# 1_P1.net
KiCad netlist of a schematic drawn in Altium Designer
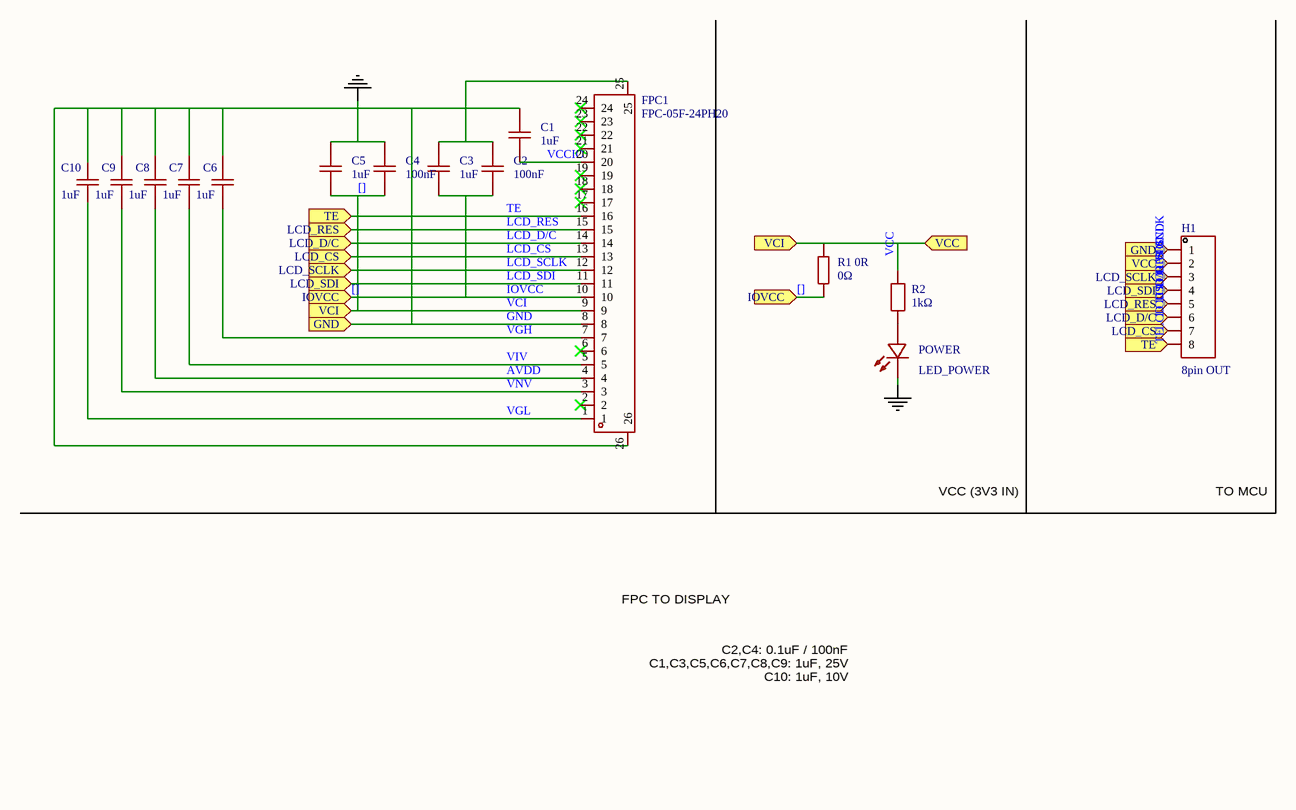
[diagram p0: 1_P1.schdoc]

(export (version "E")
  (design (tool "Eeschema 10.0.6"))
  (components
    (comp (ref "C1")
      (value "1uF")
      (footprint "C0402")
      (description "容值:1uF;精度:±10%;额定电压:25V;温度系数:X5R;")
      (fields
        (field (name "MANUFACTURER") "SAMSUNG(三星)")
        (field (name "MANUFACTURER PART") "CL05A105KA5NQNC")
      )
      (libsource (lib "altium-import") (part "root_1_CL05A105KA5NQNC_"))
    )
    (comp (ref "C2")
      (value "100nF")
      (footprint "C0402")
      (description "容值:100nF;精度:±10%;额定电压:50V;温度系数:X7R;")
      (fields
        (field (name "MANUFACTURER") "SAMSUNG(三星)")
        (field (name "MANUFACTURER PART") "CL05B104KB54PNC")
      )
      (libsource (lib "altium-import") (part "root_3_CL05B104KB54PNC_"))
    )
    (comp (ref "C3")
      (value "1uF")
      (footprint "C0402")
      (description "容值:1uF;精度:±10%;额定电压:25V;温度系数:X5R;")
      (fields
        (field (name "MANUFACTURER") "SAMSUNG(三星)")
        (field (name "MANUFACTURER PART") "CL05A105KA5NQNC")
      )
      (libsource (lib "altium-import") (part "root_3_CL05A105KA5NQNC_"))
    )
    (comp (ref "C4")
      (value "100nF")
      (footprint "C0402")
      (description "容值:100nF;精度:±10%;额定电压:50V;温度系数:X7R;")
      (fields
        (field (name "MANUFACTURER") "SAMSUNG(三星)")
        (field (name "MANUFACTURER PART") "CL05B104KB54PNC")
      )
      (libsource (lib "altium-import") (part "root_3_CL05B104KB54PNC_"))
    )
    (comp (ref "C5")
      (value "1uF")
      (footprint "C0402")
      (description "容值:1uF;精度:±10%;额定电压:25V;温度系数:X5R;")
      (fields
        (field (name "MANUFACTURER") "SAMSUNG(三星)")
        (field (name "MANUFACTURER PART") "CL05A105KA5NQNC")
      )
      (libsource (lib "altium-import") (part "root_3_CL05A105KA5NQNC_"))
    )
    (comp (ref "C6")
      (value "1uF")
      (footprint "C0402")
      (description "容值:1uF;精度:±10%;额定电压:25V;温度系数:X5R;")
      (fields
        (field (name "MANUFACTURER") "SAMSUNG(三星)")
        (field (name "MANUFACTURER PART") "CL05A105KA5NQNC")
      )
      (libsource (lib "altium-import") (part "root_3_CL05A105KA5NQNC_"))
    )
    (comp (ref "C7")
      (value "1uF")
      (footprint "C0402")
      (description "容值:1uF;精度:±10%;额定电压:25V;温度系数:X5R;")
      (fields
        (field (name "MANUFACTURER") "SAMSUNG(三星)")
        (field (name "MANUFACTURER PART") "CL05A105KA5NQNC")
      )
      (libsource (lib "altium-import") (part "root_3_CL05A105KA5NQNC_"))
    )
    (comp (ref "C8")
      (value "1uF")
      (footprint "C0402")
      (description "容值:1uF;精度:±10%;额定电压:25V;温度系数:X5R;")
      (fields
        (field (name "MANUFACTURER") "SAMSUNG(三星)")
        (field (name "MANUFACTURER PART") "CL05A105KA5NQNC")
      )
      (libsource (lib "altium-import") (part "root_3_CL05A105KA5NQNC_"))
    )
    (comp (ref "C9")
      (value "1uF")
      (footprint "C0402")
      (description "容值:1uF;精度:±10%;额定电压:25V;温度系数:X5R;")
      (fields
        (field (name "MANUFACTURER") "SAMSUNG(三星)")
        (field (name "MANUFACTURER PART") "CL05A105KA5NQNC")
      )
      (libsource (lib "altium-import") (part "root_3_CL05A105KA5NQNC_"))
    )
    (comp (ref "C10")
      (value "1uF")
      (footprint "C0402")
      (description "容值:1uF;精度:±10%;额定电压:10V;温度系数:X5R;")
      (fields
        (field (name "MANUFACTURER") "SAMSUNG(三星)")
        (field (name "MANUFACTURER PART") "CL05A105KP5NNNC")
      )
      (libsource (lib "altium-import") (part "root_3_CL05A105KP5NNNC_"))
    )
    (comp (ref "FPC1")
      (value "FPC-05F-24PH20")
      (footprint "FPC-SMD_24P-P0.50_FPC-05F-24PH20")
      (description "锁定特性:翻盖式;触点类型:卧贴;触点数量:24P;间距:0.5mm;安装方式:下接;工作温度:-25℃~+85℃;")
      (fields (field (name "MANUFACTURER") "XUNPU(讯普)"))
      (libsource (lib "altium-import") (part "root_2_mirrored_FPC-05F-24PH20_"))
    )
    (comp (ref "H1")
      (value "8pin OUT")
      (footprint "HDR-TH_8P-P2.54-V-M")
      (fields (field (name "MANUFACTURER") "Ckmtw(灿科盟)"))
      (libsource (lib "altium-import") (part "root_0_B-2100S08P-A110_"))
    )
    (comp (ref "POWER")
      (value "LED_POWER")
      (footprint "LED0603-RD-YELLOW")
      (fields (field (name "MANUFACTURER") "LITEON(光宝)"))
      (libsource (lib "altium-import") (part "root_1_LTST-C191KSKT_"))
    )
    (comp (ref "R1 0R")
      (value "0Ω")
      (footprint "R0805")
      (description "电阻类型:厚膜电阻;阻值:0Ω;精度:±1%;功率:125mW;工作电压:150V;温度系数:±800ppm/℃;")
      (fields
        (field (name "MANUFACTURER") "UNI-ROYAL(厚声)")
        (field (name "MANUFACTURER PART") "0805W8F0000T5E")
      )
      (libsource (lib "altium-import") (part "root_1_0805W8F0000T5E_"))
    )
    (comp (ref "R2")
      (value "1kΩ")
      (footprint "R0805")
      (description "电阻类型:厚膜电阻;阻值:1kΩ;精度:±5%;功率:125mW;工作电压:150V;温度系数:±100ppm/℃;")
      (fields (field (name "MANUFACTURER") "FOJAN(富捷)") (field (name "MANUFACTURER PART") "FRR0805J102 TS"))
      (libsource (lib "altium-import") (part "root_1_FRR0805J102 TS_"))
    )
  )
  (nets
    (net (code "1") (name "/AVDD") (class "Default")
      (node (ref "C8") (pin "2") (pinfunction "2_2") (pintype "passive"))
      (node (ref "FPC1") (pin "4") (pinfunction "4_4") (pintype "passive"))
    )
    (net (code "2") (name "/IOVCC") (class "Default")
      (node (ref "C2") (pin "2") (pinfunction "2_2") (pintype "passive"))
      (node (ref "C3") (pin "2") (pinfunction "2_2") (pintype "passive"))
      (node (ref "C4") (pin "2") (pinfunction "2_2") (pintype "passive"))
      (node (ref "C5") (pin "2") (pinfunction "2_2") (pintype "passive"))
      (node (ref "FPC1") (pin "10") (pinfunction "10_10") (pintype "passive"))
      (node (ref "FPC1") (pin "9") (pinfunction "9_9") (pintype "passive"))
      (node (ref "H1") (pin "2") (pinfunction "2_2") (pintype "passive"))
      (node (ref "R1 0R") (pin "1") (pinfunction "1_1") (pintype "passive"))
      (node (ref "R1 0R") (pin "2") (pinfunction "2_2") (pintype "passive"))
      (node (ref "R2") (pin "2") (pinfunction "2_2") (pintype "passive"))
    )
    (net (code "3") (name "/LCD_CS") (class "Default")
      (node (ref "FPC1") (pin "13") (pinfunction "13_13") (pintype "passive"))
      (node (ref "H1") (pin "7") (pinfunction "7_7") (pintype "passive"))
    )
    (net (code "4") (name "/LCD_D{slash}C") (class "Default")
      (node (ref "FPC1") (pin "14") (pinfunction "14_14") (pintype "passive"))
      (node (ref "H1") (pin "6") (pinfunction "6_6") (pintype "passive"))
    )
    (net (code "5") (name "/LCD_RES") (class "Default")
      (node (ref "FPC1") (pin "15") (pinfunction "15_15") (pintype "passive"))
      (node (ref "H1") (pin "5") (pinfunction "5_5") (pintype "passive"))
    )
    (net (code "6") (name "/LCD_SCLK") (class "Default")
      (node (ref "FPC1") (pin "12") (pinfunction "12_12") (pintype "passive"))
      (node (ref "H1") (pin "3") (pinfunction "3_3") (pintype "passive"))
    )
    (net (code "7") (name "/LCD_SDI") (class "Default")
      (node (ref "FPC1") (pin "11") (pinfunction "11_11") (pintype "passive"))
      (node (ref "H1") (pin "4") (pinfunction "4_4") (pintype "passive"))
    )
    (net (code "8") (name "/TE") (class "Default")
      (node (ref "FPC1") (pin "16") (pinfunction "16_16") (pintype "passive"))
      (node (ref "H1") (pin "8") (pinfunction "8_8") (pintype "passive"))
    )
    (net (code "9") (name "/VCCIO") (class "Default")
      (node (ref "C1") (pin "1") (pinfunction "1_1") (pintype "passive"))
      (node (ref "FPC1") (pin "20") (pinfunction "20_20") (pintype "passive"))
    )
    (net (code "10") (name "/VGH") (class "Default")
      (node (ref "C6") (pin "2") (pinfunction "2_2") (pintype "passive"))
      (node (ref "FPC1") (pin "7") (pinfunction "7_7") (pintype "passive"))
    )
    (net (code "11") (name "/VGL") (class "Default")
      (node (ref "C10") (pin "2") (pinfunction "2_2") (pintype "passive"))
      (node (ref "FPC1") (pin "1") (pinfunction "1_1") (pintype "passive"))
    )
    (net (code "12") (name "/VIV") (class "Default")
      (node (ref "C7") (pin "2") (pinfunction "2_2") (pintype "passive"))
      (node (ref "FPC1") (pin "5") (pinfunction "5_5") (pintype "passive"))
    )
    (net (code "13") (name "/VNV") (class "Default")
      (node (ref "C9") (pin "2") (pinfunction "2_2") (pintype "passive"))
      (node (ref "FPC1") (pin "3") (pinfunction "3_3") (pintype "passive"))
    )
    (net (code "14") (name "GND") (class "Default")
      (node (ref "C1") (pin "2") (pinfunction "2_2") (pintype "passive"))
      (node (ref "C10") (pin "1") (pinfunction "1_1") (pintype "passive"))
      (node (ref "C2") (pin "1") (pinfunction "1_1") (pintype "passive"))
      (node (ref "C3") (pin "1") (pinfunction "1_1") (pintype "passive"))
      (node (ref "C4") (pin "1") (pinfunction "1_1") (pintype "passive"))
      (node (ref "C5") (pin "1") (pinfunction "1_1") (pintype "passive"))
      (node (ref "C6") (pin "1") (pinfunction "1_1") (pintype "passive"))
      (node (ref "C7") (pin "1") (pinfunction "1_1") (pintype "passive"))
      (node (ref "C8") (pin "1") (pinfunction "1_1") (pintype "passive"))
      (node (ref "C9") (pin "1") (pinfunction "1_1") (pintype "passive"))
      (node (ref "FPC1") (pin "25") (pinfunction "25_25") (pintype "passive"))
      (node (ref "FPC1") (pin "26") (pinfunction "26_26") (pintype "passive"))
      (node (ref "FPC1") (pin "8") (pinfunction "8_8") (pintype "passive"))
      (node (ref "H1") (pin "1") (pinfunction "1_1") (pintype "passive"))
      (node (ref "POWER") (pin "1") (pinfunction "-_1") (pintype "passive"))
    )
    (net (code "15") (name "Net-(POWER-+)") (class "Default")
      (node (ref "POWER") (pin "2") (pinfunction "+_2") (pintype "passive"))
      (node (ref "R2") (pin "1") (pinfunction "1_1") (pintype "passive"))
    )
    (net (code "16") (name "unconnected-(FPC1-Pad2)") (class "Default")
      (node (ref "FPC1") (pin "2") (pinfunction "2_2") (pintype "passive+no_connect"))
    )
    (net (code "17") (name "unconnected-(FPC1-Pad6)") (class "Default")
      (node (ref "FPC1") (pin "6") (pinfunction "6_6") (pintype "passive+no_connect"))
    )
    (net (code "18") (name "unconnected-(FPC1-Pad17)") (class "Default")
      (node (ref "FPC1") (pin "17") (pinfunction "17_17") (pintype "passive+no_connect"))
    )
    (net (code "19") (name "unconnected-(FPC1-Pad18)") (class "Default")
      (node (ref "FPC1") (pin "18") (pinfunction "18_18") (pintype "passive+no_connect"))
    )
    (net (code "20") (name "unconnected-(FPC1-Pad19)") (class "Default")
      (node (ref "FPC1") (pin "19") (pinfunction "19_19") (pintype "passive+no_connect"))
    )
    (net (code "21") (name "unconnected-(FPC1-Pad21)") (class "Default")
      (node (ref "FPC1") (pin "21") (pinfunction "21_21") (pintype "passive+no_connect"))
    )
    (net (code "22") (name "unconnected-(FPC1-Pad22)") (class "Default")
      (node (ref "FPC1") (pin "22") (pinfunction "22_22") (pintype "passive+no_connect"))
    )
    (net (code "23") (name "unconnected-(FPC1-Pad23)") (class "Default")
      (node (ref "FPC1") (pin "23") (pinfunction "23_23") (pintype "passive+no_connect"))
    )
    (net (code "24") (name "unconnected-(FPC1-Pad24)") (class "Default")
      (node (ref "FPC1") (pin "24") (pinfunction "24_24") (pintype "passive+no_connect"))
    )
  )
)
